# filter.net
KiCad netlist of a schematic drawn in Altium Designer
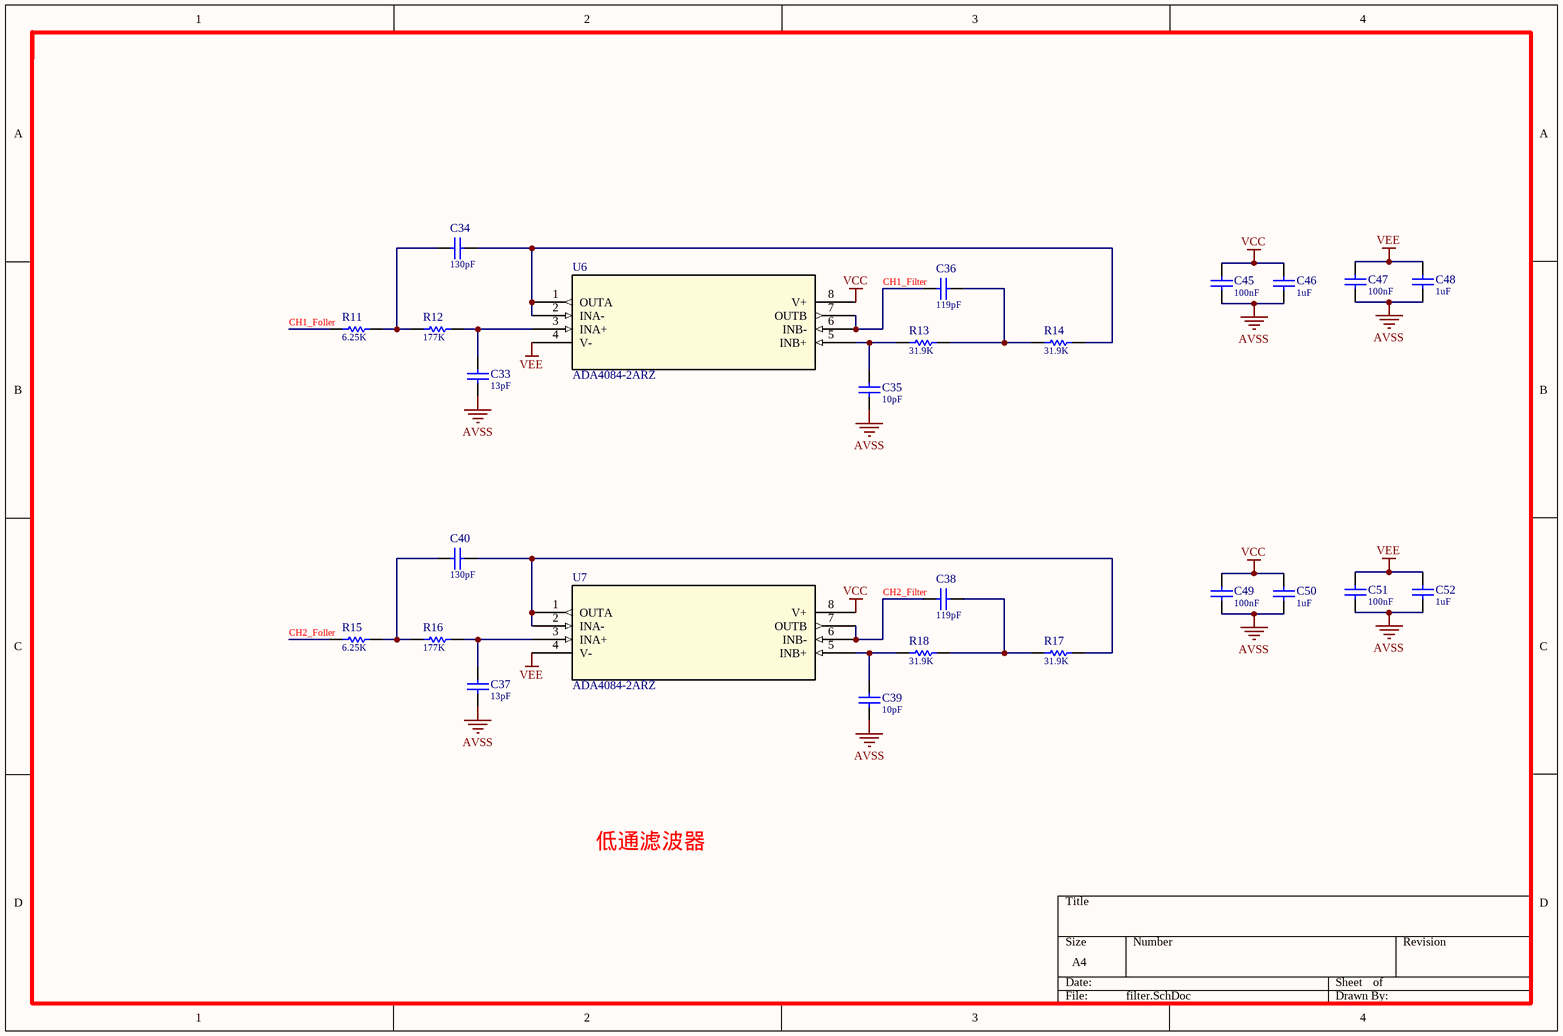
[diagram p0: filter.SchDoc]

(export (version "E")
  (design (tool "Eeschema 10.0.6"))
  (components
    (comp (ref "C33")
      (value "13pF")
      (footprint "C0603-L")
      (description "贴片瓷片电容")
      (fields (field (name "Comment") "Cap-S"))
      (libsource (lib "XuZhe") (part "Cap-S"))
    )
    (comp (ref "C34")
      (value "130pF")
      (footprint "C0603-L")
      (description "贴片瓷片电容")
      (fields (field (name "Comment") "Cap-S"))
      (libsource (lib "XuZhe") (part "Cap-S"))
    )
    (comp (ref "C35")
      (value "10pF")
      (footprint "C0603-L")
      (description "贴片瓷片电容")
      (fields (field (name "Comment") "Cap-S"))
      (libsource (lib "XuZhe") (part "Cap-S"))
    )
    (comp (ref "C36")
      (value "119pF")
      (footprint "C0603-L")
      (description "贴片瓷片电容")
      (fields (field (name "Comment") "Cap-S"))
      (libsource (lib "XuZhe") (part "Cap-S"))
    )
    (comp (ref "C37")
      (value "13pF")
      (footprint "C0603-L")
      (description "贴片瓷片电容")
      (fields (field (name "Comment") "Cap-S"))
      (libsource (lib "XuZhe") (part "Cap-S"))
    )
    (comp (ref "C38")
      (value "119pF")
      (footprint "C0603-L")
      (description "贴片瓷片电容")
      (fields (field (name "Comment") "Cap-S"))
      (libsource (lib "XuZhe") (part "Cap-S"))
    )
    (comp (ref "C39")
      (value "10pF")
      (footprint "C0603-L")
      (description "贴片瓷片电容")
      (fields (field (name "Comment") "Cap-S"))
      (libsource (lib "XuZhe") (part "Cap-S"))
    )
    (comp (ref "C40")
      (value "130pF")
      (footprint "C0603-L")
      (description "贴片瓷片电容")
      (fields (field (name "Comment") "Cap-S"))
      (libsource (lib "XuZhe") (part "Cap-S"))
    )
    (comp (ref "C45")
      (value "100nF")
      (footprint "C0603-L")
      (description "贴片瓷片电容")
      (fields (field (name "Comment") "Cap-S"))
      (libsource (lib "XuZhe") (part "Cap-S"))
    )
    (comp (ref "C46")
      (value "1uF")
      (footprint "C0603-L")
      (description "贴片瓷片电容")
      (fields (field (name "Comment") "Cap-S"))
      (libsource (lib "XuZhe") (part "Cap-S"))
    )
    (comp (ref "C47")
      (value "100nF")
      (footprint "C0603-L")
      (description "贴片瓷片电容")
      (fields (field (name "Comment") "Cap-S"))
      (libsource (lib "XuZhe") (part "Cap-S"))
    )
    (comp (ref "C48")
      (value "1uF")
      (footprint "C0603-L")
      (description "贴片瓷片电容")
      (fields (field (name "Comment") "Cap-S"))
      (libsource (lib "XuZhe") (part "Cap-S"))
    )
    (comp (ref "C49")
      (value "100nF")
      (footprint "C0603-L")
      (description "贴片瓷片电容")
      (fields (field (name "Comment") "Cap-S"))
      (libsource (lib "XuZhe") (part "Cap-S"))
    )
    (comp (ref "C50")
      (value "1uF")
      (footprint "C0603-L")
      (description "贴片瓷片电容")
      (fields (field (name "Comment") "Cap-S"))
      (libsource (lib "XuZhe") (part "Cap-S"))
    )
    (comp (ref "C51")
      (value "100nF")
      (footprint "C0603-L")
      (description "贴片瓷片电容")
      (fields (field (name "Comment") "Cap-S"))
      (libsource (lib "XuZhe") (part "Cap-S"))
    )
    (comp (ref "C52")
      (value "1uF")
      (footprint "C0603-L")
      (description "贴片瓷片电容")
      (fields (field (name "Comment") "Cap-S"))
      (libsource (lib "XuZhe") (part "Cap-S"))
    )
    (comp (ref "R11")
      (value "6.25K")
      (footprint "R0603-L")
      (description "贴片电阻")
      (fields (field (name "Comment") "R"))
      (libsource (lib "XuZhe") (part "Res"))
    )
    (comp (ref "R12")
      (value "177K")
      (footprint "R0603-L")
      (description "贴片电阻")
      (fields (field (name "Comment") "R"))
      (libsource (lib "XuZhe") (part "Res"))
    )
    (comp (ref "R13")
      (value "31.9K")
      (footprint "R0603-L")
      (description "贴片电阻")
      (fields (field (name "Comment") "R"))
      (libsource (lib "XuZhe") (part "Res"))
    )
    (comp (ref "R14")
      (value "31.9K")
      (footprint "R0603-L")
      (description "贴片电阻")
      (fields (field (name "Comment") "R"))
      (libsource (lib "XuZhe") (part "Res"))
    )
    (comp (ref "R15")
      (value "6.25K")
      (footprint "R0603-L")
      (description "贴片电阻")
      (fields (field (name "Comment") "R"))
      (libsource (lib "XuZhe") (part "Res"))
    )
    (comp (ref "R16")
      (value "177K")
      (footprint "R0603-L")
      (description "贴片电阻")
      (fields (field (name "Comment") "R"))
      (libsource (lib "XuZhe") (part "Res"))
    )
    (comp (ref "R17")
      (value "31.9K")
      (footprint "R0603-L")
      (description "贴片电阻")
      (fields (field (name "Comment") "R"))
      (libsource (lib "XuZhe") (part "Res"))
    )
    (comp (ref "R18")
      (value "31.9K")
      (footprint "R0603-L")
      (description "贴片电阻")
      (fields (field (name "Comment") "R"))
      (libsource (lib "XuZhe") (part "Res"))
    )
    (comp (ref "U6")
      (value "ADA4084-2ARZ")
      (footprint "R_8_ADI")
      (description "No Description Available")
      (fields (field (name "COPYRIGHT") "Copyright (C) 2021 Ultra Librarian. All rights reserved."))
      (libsource (lib "ADA4084-2ARZ") (part "ADA4084-2ARZ"))
    )
    (comp (ref "U7")
      (value "ADA4084-2ARZ")
      (footprint "R_8_ADI")
      (description "No Description Available")
      (fields (field (name "COPYRIGHT") "Copyright (C) 2021 Ultra Librarian. All rights reserved."))
      (libsource (lib "ADA4084-2ARZ") (part "ADA4084-2ARZ"))
    )
  )
  (nets
    (net (code "1") (name "/CH1_Filter") (class "Default")
      (node (ref "C36") (pin "2") (pinfunction "2_2") (pintype "passive"))
      (node (ref "U6") (pin "6") (pinfunction "INB-_6") (pintype "input"))
      (node (ref "U6") (pin "7") (pinfunction "OUTB_7") (pintype "output"))
    )
    (net (code "2") (name "/CH1_Foller") (class "Default")
      (node (ref "R11") (pin "1") (pinfunction "1_1") (pintype "passive"))
    )
    (net (code "3") (name "/CH2_Filter") (class "Default")
      (node (ref "C38") (pin "2") (pinfunction "2_2") (pintype "passive"))
      (node (ref "U7") (pin "6") (pinfunction "INB-_6") (pintype "input"))
      (node (ref "U7") (pin "7") (pinfunction "OUTB_7") (pintype "output"))
    )
    (net (code "4") (name "/CH2_Foller") (class "Default")
      (node (ref "R15") (pin "1") (pinfunction "1_1") (pintype "passive"))
    )
    (net (code "5") (name "AVSS") (class "Default")
      (node (ref "C33") (pin "1") (pinfunction "1_1") (pintype "passive"))
      (node (ref "C35") (pin "1") (pinfunction "1_1") (pintype "passive"))
      (node (ref "C37") (pin "1") (pinfunction "1_1") (pintype "passive"))
      (node (ref "C39") (pin "1") (pinfunction "1_1") (pintype "passive"))
      (node (ref "C45") (pin "1") (pinfunction "1_1") (pintype "passive"))
      (node (ref "C46") (pin "1") (pinfunction "1_1") (pintype "passive"))
      (node (ref "C47") (pin "1") (pinfunction "1_1") (pintype "passive"))
      (node (ref "C48") (pin "1") (pinfunction "1_1") (pintype "passive"))
      (node (ref "C49") (pin "1") (pinfunction "1_1") (pintype "passive"))
      (node (ref "C50") (pin "1") (pinfunction "1_1") (pintype "passive"))
      (node (ref "C51") (pin "1") (pinfunction "1_1") (pintype "passive"))
      (node (ref "C52") (pin "1") (pinfunction "1_1") (pintype "passive"))
    )
    (net (code "6") (name "Net-(C34-Pad1)") (class "Default")
      (node (ref "C34") (pin "1") (pinfunction "1_1") (pintype "passive"))
      (node (ref "R11") (pin "2") (pinfunction "2_2") (pintype "passive"))
      (node (ref "R12") (pin "1") (pinfunction "1_1") (pintype "passive"))
    )
    (net (code "7") (name "Net-(C36-Pad1)") (class "Default")
      (node (ref "C36") (pin "1") (pinfunction "1_1") (pintype "passive"))
      (node (ref "R13") (pin "2") (pinfunction "2_2") (pintype "passive"))
      (node (ref "R14") (pin "1") (pinfunction "1_1") (pintype "passive"))
    )
    (net (code "8") (name "Net-(C38-Pad1)") (class "Default")
      (node (ref "C38") (pin "1") (pinfunction "1_1") (pintype "passive"))
      (node (ref "R17") (pin "1") (pinfunction "1_1") (pintype "passive"))
      (node (ref "R18") (pin "2") (pinfunction "2_2") (pintype "passive"))
    )
    (net (code "9") (name "Net-(C40-Pad1)") (class "Default")
      (node (ref "C40") (pin "1") (pinfunction "1_1") (pintype "passive"))
      (node (ref "R15") (pin "2") (pinfunction "2_2") (pintype "passive"))
      (node (ref "R16") (pin "1") (pinfunction "1_1") (pintype "passive"))
    )
    (net (code "10") (name "Net-(U6-INA+)") (class "Default")
      (node (ref "C33") (pin "2") (pinfunction "2_2") (pintype "passive"))
      (node (ref "R12") (pin "2") (pinfunction "2_2") (pintype "passive"))
      (node (ref "U6") (pin "3") (pinfunction "INA+_3") (pintype "input"))
    )
    (net (code "11") (name "Net-(U6-INA-)") (class "Default")
      (node (ref "C34") (pin "2") (pinfunction "2_2") (pintype "passive"))
      (node (ref "R14") (pin "2") (pinfunction "2_2") (pintype "passive"))
      (node (ref "U6") (pin "1") (pinfunction "OUTA_1") (pintype "output"))
      (node (ref "U6") (pin "2") (pinfunction "INA-_2") (pintype "input"))
    )
    (net (code "12") (name "Net-(U6-INB+)") (class "Default")
      (node (ref "C35") (pin "2") (pinfunction "2_2") (pintype "passive"))
      (node (ref "R13") (pin "1") (pinfunction "1_1") (pintype "passive"))
      (node (ref "U6") (pin "5") (pinfunction "INB+_5") (pintype "input"))
    )
    (net (code "13") (name "Net-(U7-INA+)") (class "Default")
      (node (ref "C37") (pin "2") (pinfunction "2_2") (pintype "passive"))
      (node (ref "R16") (pin "2") (pinfunction "2_2") (pintype "passive"))
      (node (ref "U7") (pin "3") (pinfunction "INA+_3") (pintype "input"))
    )
    (net (code "14") (name "Net-(U7-INA-)") (class "Default")
      (node (ref "C40") (pin "2") (pinfunction "2_2") (pintype "passive"))
      (node (ref "R17") (pin "2") (pinfunction "2_2") (pintype "passive"))
      (node (ref "U7") (pin "1") (pinfunction "OUTA_1") (pintype "output"))
      (node (ref "U7") (pin "2") (pinfunction "INA-_2") (pintype "input"))
    )
    (net (code "15") (name "Net-(U7-INB+)") (class "Default")
      (node (ref "C39") (pin "2") (pinfunction "2_2") (pintype "passive"))
      (node (ref "R18") (pin "1") (pinfunction "1_1") (pintype "passive"))
      (node (ref "U7") (pin "5") (pinfunction "INB+_5") (pintype "input"))
    )
    (net (code "16") (name "VCC") (class "Default")
      (node (ref "C45") (pin "2") (pinfunction "2_2") (pintype "passive"))
      (node (ref "C46") (pin "2") (pinfunction "2_2") (pintype "passive"))
      (node (ref "C49") (pin "2") (pinfunction "2_2") (pintype "passive"))
      (node (ref "C50") (pin "2") (pinfunction "2_2") (pintype "passive"))
      (node (ref "U6") (pin "8") (pinfunction "V+_8") (pintype "power_in"))
      (node (ref "U7") (pin "8") (pinfunction "V+_8") (pintype "power_in"))
    )
    (net (code "17") (name "VEE") (class "Default")
      (node (ref "C47") (pin "2") (pinfunction "2_2") (pintype "passive"))
      (node (ref "C48") (pin "2") (pinfunction "2_2") (pintype "passive"))
      (node (ref "C51") (pin "2") (pinfunction "2_2") (pintype "passive"))
      (node (ref "C52") (pin "2") (pinfunction "2_2") (pintype "passive"))
      (node (ref "U6") (pin "4") (pinfunction "V-_4") (pintype "power_in"))
      (node (ref "U7") (pin "4") (pinfunction "V-_4") (pintype "power_in"))
    )
  )
)
